# SENSOR.net
KiCad netlist of a schematic drawn in Altium Designer
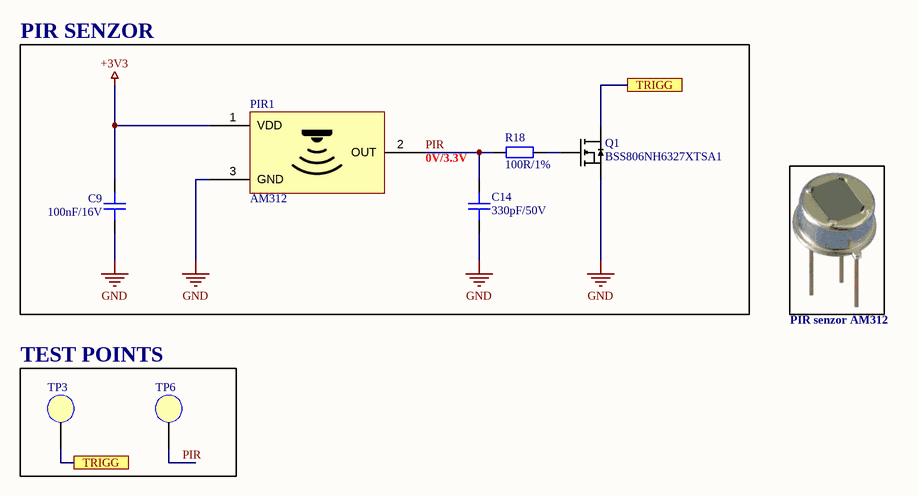
[diagram p0: SENSOR.SchDoc]

(export (version "E")
  (design (tool "Eeschema 10.0.6"))
  (components
    (comp (ref "C9")
      (value "100nF/16V")
      (footprint "CAP_0603")
      (description "0.1 µF ±10% 16V Ceramic Capacitor X7R 0603 (1608 Metric)")
      (fields (field (name "MPN") "CC0603KRX7R7BB104"))
      (libsource (lib "Library-AutomatskoOsvetljenje") (part "100nF/16V"))
    )
    (comp (ref "C14")
      (value "330pF/50V")
      (footprint "CAP_0603")
      (description "330 pF ±10% 50V Ceramic Capacitor X7R 0603 (1608 Metric)")
      (fields (field (name "MPN") "C0603C331K5RACTU"))
      (libsource (lib "Library-AutomatskoOsvetljenje") (part "330pF/50V"))
    )
    (comp (ref "PIR1")
      (value "AM312")
      (footprint "AM312")
      (description "AM312 PIR sensor")
      (libsource (lib "Library-AutomatskoOsvetljenje") (part "AM312"))
    )
    (comp (ref "Q1")
      (value "BSS806NH6327XTSA1")
      (footprint "SOT23-3")
      (description "N-Channel 20 V 2.3A (Ta) 500mW (Ta) Surface Mount PG-SOT23")
      (libsource (lib "Library-AutomatskoOsvetljenje") (part "BSS806NH6327XTSA1_NMOS"))
    )
    (comp (ref "R18")
      (value "100R/1%")
      (footprint "RES_0603")
      (description "100 Ohms ±1% 0.1W, 1/10W Chip Resistor 0603 (1608 Metric) Automotive AEC-Q200 Thick Film")
      (fields (field (name "MPN") "ERJ-3EKF1000V"))
      (libsource (lib "Library-AutomatskoOsvetljenje") (part "100R/1%"))
    )
    (comp (ref "TP3")
      (value "TESTPOINT")
      (footprint "TESTPOINT")
      (description "White PC Test Point, Miniature Phosphor Bronze Silver Plating Through Hole Mounting Type")
      (fields (field (name "MPN") "5002"))
      (libsource (lib "Library-AutomatskoOsvetljenje") (part "TESTPOINT"))
    )
    (comp (ref "TP6")
      (value "TESTPOINT")
      (footprint "TESTPOINT")
      (description "White PC Test Point, Miniature Phosphor Bronze Silver Plating Through Hole Mounting Type")
      (fields (field (name "MPN") "5002"))
      (libsource (lib "Library-AutomatskoOsvetljenje") (part "TESTPOINT"))
    )
  )
  (nets
    (net (code "1") (name "+3V3") (class "Default")
      (node (ref "C9") (pin "2") (pinfunction "2_2") (pintype "passive"))
      (node (ref "PIR1") (pin "1") (pinfunction "VDD_1") (pintype "passive"))
    )
    (net (code "2") (name "/PIR") (class "Default")
      (node (ref "C14") (pin "2") (pinfunction "2_2") (pintype "passive"))
      (node (ref "PIR1") (pin "2") (pinfunction "OUT_2") (pintype "passive"))
      (node (ref "R18") (pin "1") (pinfunction "1_1") (pintype "passive"))
      (node (ref "TP6") (pin "1") (pinfunction "TP_1") (pintype "passive"))
    )
    (net (code "3") (name "/TRIGG") (class "Default")
      (node (ref "Q1") (pin "3") (pinfunction "3_3") (pintype "passive"))
      (node (ref "TP3") (pin "1") (pinfunction "TP_1") (pintype "passive"))
    )
    (net (code "4") (name "GND") (class "Default")
      (node (ref "C14") (pin "1") (pinfunction "1_1") (pintype "passive"))
      (node (ref "C9") (pin "1") (pinfunction "1_1") (pintype "passive"))
      (node (ref "PIR1") (pin "3") (pinfunction "GND_3") (pintype "passive"))
      (node (ref "Q1") (pin "2") (pinfunction "2_2") (pintype "passive"))
    )
    (net (code "5") (name "Net-(Q1-11)") (class "Default")
      (node (ref "Q1") (pin "1") (pinfunction "11_1") (pintype "passive"))
      (node (ref "R18") (pin "2") (pinfunction "2_2") (pintype "passive"))
    )
  )
)
